# shield_SIM7000E.net
KiCad netlist of a schematic drawn in EAGLE
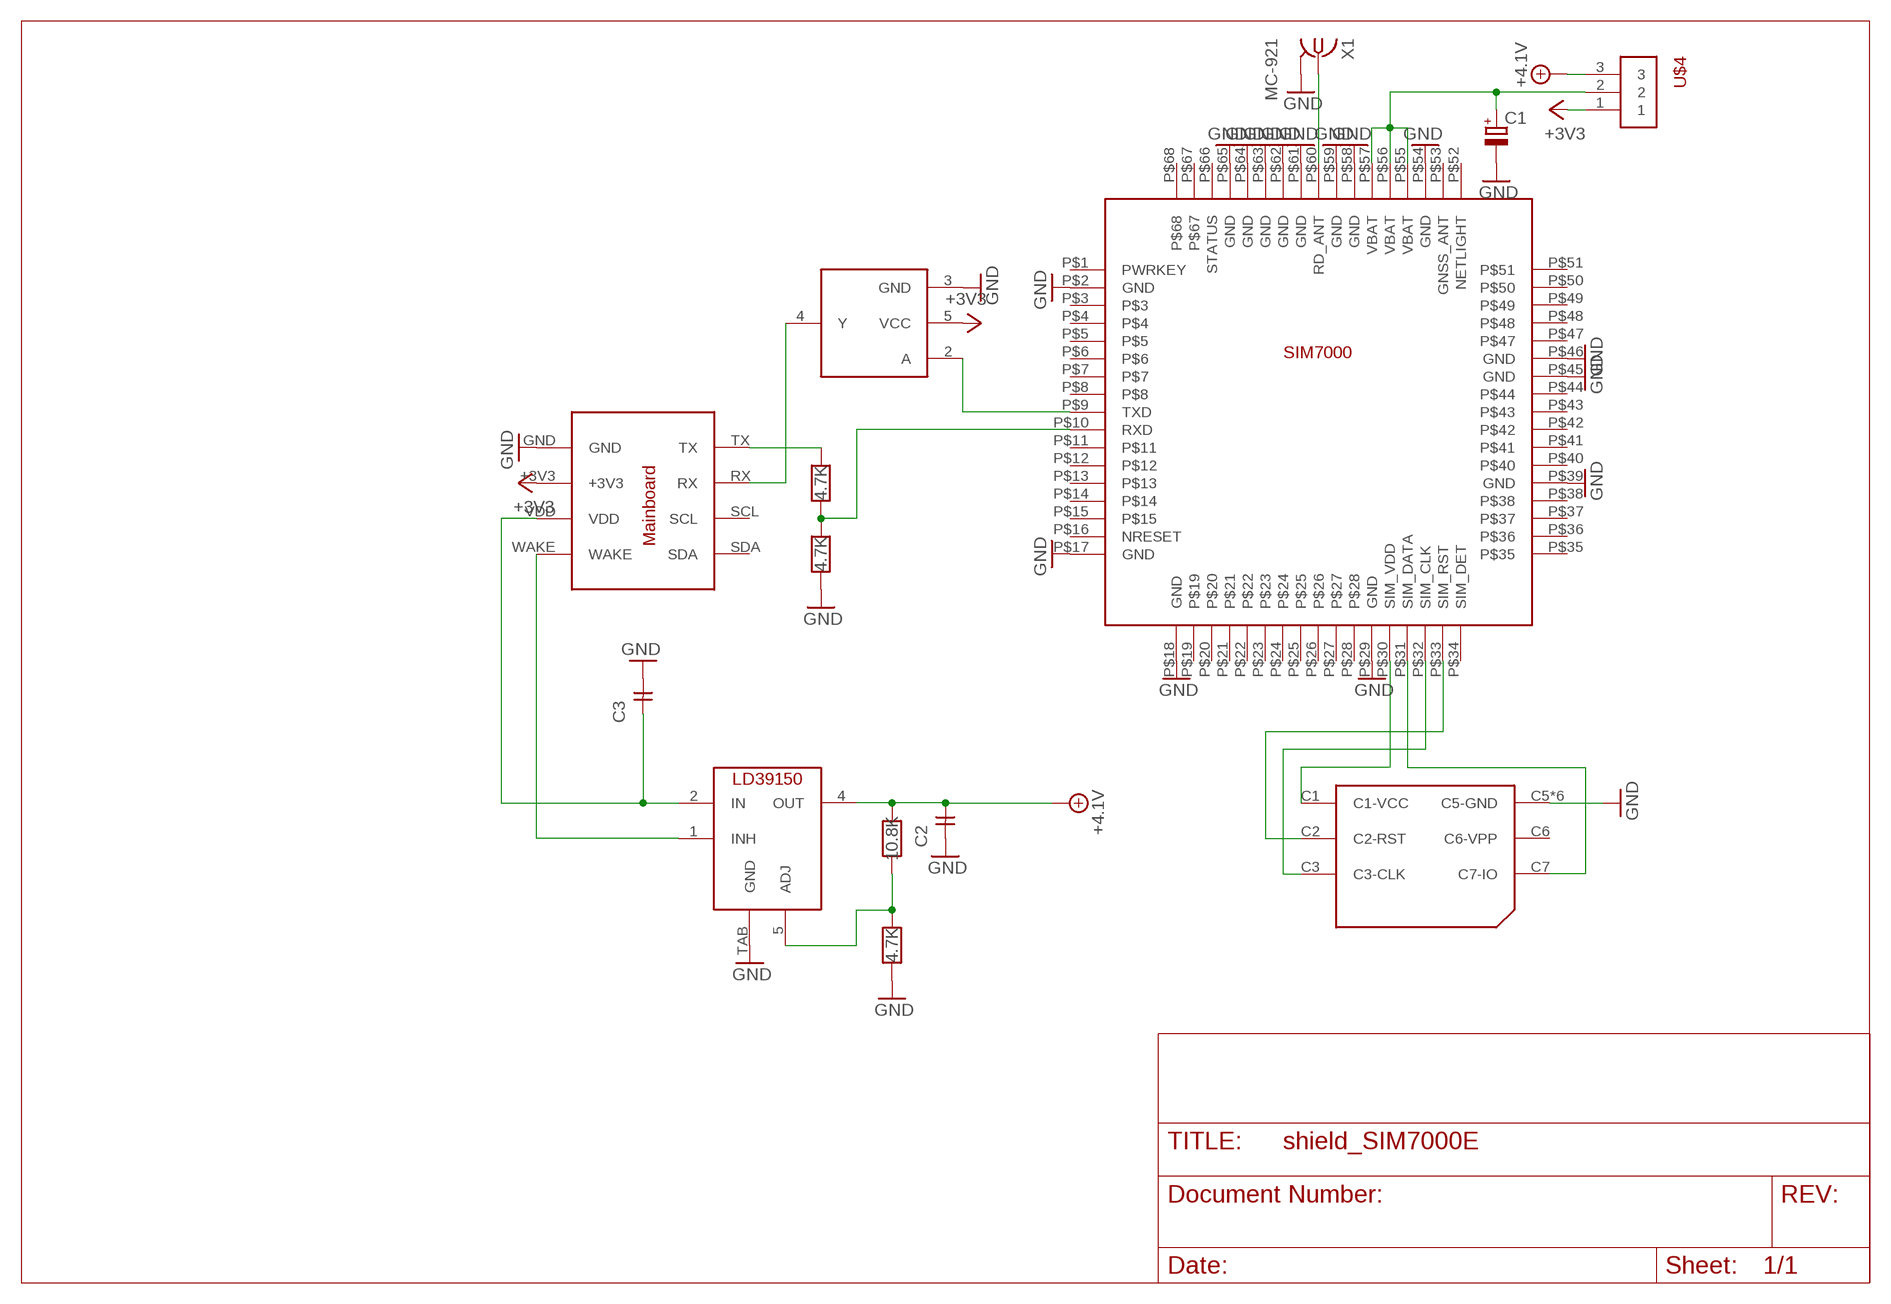
[diagram p0: schematic, sheet 1]

(export (version "E")
  (design (tool "Eeschema 10.0.6"))
  (components
    (comp (ref "C1")
      (value "CPOL-EUE5-13")
      (footprint "eagle-import:E5-13")
      (libsource (lib "eagle-import") (part "CPOL-EUE5-13"))
    )
    (comp (ref "C2")
      (value "CSMD_1206")
      (footprint "eagle-import:SMD_RC_1206")
      (libsource (lib "eagle-import") (part "CSMD_1206"))
    )
    (comp (ref "C3")
      (value "CSMD_1206")
      (footprint "eagle-import:SMD_RC_1206")
      (libsource (lib "eagle-import") (part "CSMD_1206"))
    )
    (comp (ref "R1")
      (value "10.8K")
      (footprint "eagle-import:SMD_RC_1206")
      (libsource (lib "eagle-import") (part "RSMD_1206"))
    )
    (comp (ref "R2")
      (value "4.7K")
      (footprint "eagle-import:SMD_RC_1206")
      (libsource (lib "eagle-import") (part "RSMD_1206"))
    )
    (comp (ref "R3")
      (value "4.7K")
      (footprint "eagle-import:SMD_RC_1206")
      (libsource (lib "eagle-import") (part "RSMD_1206"))
    )
    (comp (ref "R4")
      (value "4.7K")
      (footprint "eagle-import:SMD_RC_1206")
      (libsource (lib "eagle-import") (part "RSMD_1206"))
    )
    (comp (ref "U$1")
      (value "SHIELD")
      (footprint "eagle-import:SHIELD")
      (libsource (lib "eagle-import") (part "SHIELD"))
    )
    (comp (ref "U$2")
      (value "LD39150PT-R")
      (footprint "eagle-import:PPAK")
      (libsource (lib "eagle-import") (part "LD39150PT-R"))
    )
    (comp (ref "U$3")
      (value "SIM7000")
      (footprint "eagle-import:SIM7000")
      (libsource (lib "eagle-import") (part "SIM7000"))
    )
    (comp (ref "U$4")
      (value "HEADER_1X3")
      (footprint "eagle-import:HEADER_1X3")
      (libsource (lib "eagle-import") (part "HEADER_1X3"))
    )
    (comp (ref "U$5")
      (value "SN75LV1T34")
      (footprint "eagle-import:SOT23-5L-SIMPLE")
      (libsource (lib "eagle-import") (part "SN75LV1T34"))
    )
    (comp (ref "U$6")
      (value "SIM_SCYT")
      (footprint "eagle-import:SIM_SCYT")
      (libsource (lib "eagle-import") (part "SIM_SCYT"))
    )
    (comp (ref "X1")
      (value "MC-921")
      (footprint "eagle-import:MC-921")
      (libsource (lib "eagle-import") (part "MC-921"))
    )
  )
  (nets
    (net (code "1") (name "+3V3") (class "Default")
      (node (ref "U$1") (pin "+3V3") (pinfunction "+3V3_+3V3") (pintype "power_in"))
      (node (ref "U$4") (pin "1") (pinfunction "1_1") (pintype "passive"))
      (node (ref "U$5") (pin "5") (pinfunction "VCC_5") (pintype "bidirectional"))
    )
    (net (code "2") (name "+4.1V") (class "Default")
      (node (ref "C2") (pin "P$2") (pinfunction "2_P$2") (pintype "passive"))
      (node (ref "R1") (pin "P$1") (pinfunction "P$1_P$1") (pintype "passive"))
      (node (ref "U$2") (pin "4") (pinfunction "OUT_4") (pintype "power_in"))
      (node (ref "U$4") (pin "3") (pinfunction "3_3") (pintype "passive"))
    )
    (net (code "3") (name "GND") (class "Default")
      (node (ref "C1") (pin "-") (pinfunction "-_-") (pintype "passive"))
      (node (ref "C2") (pin "P$1") (pinfunction "1_P$1") (pintype "passive"))
      (node (ref "C3") (pin "P$2") (pinfunction "2_P$2") (pintype "passive"))
      (node (ref "R2") (pin "P$2") (pinfunction "P$2_P$2") (pintype "passive"))
      (node (ref "R4") (pin "P$1") (pinfunction "P$1_P$1") (pintype "passive"))
      (node (ref "U$1") (pin "GND") (pinfunction "GND_GND") (pintype "power_in"))
      (node (ref "U$2") (pin "TAB") (pinfunction "GND_TAB") (pintype "power_in"))
      (node (ref "U$3") (pin "P$17") (pinfunction "GND_P$17") (pintype "power_in"))
      (node (ref "U$3") (pin "P$18") (pinfunction "GND_P$18") (pintype "bidirectional"))
      (node (ref "U$3") (pin "P$2") (pinfunction "GND_P$2") (pintype "power_in"))
      (node (ref "U$3") (pin "P$29") (pinfunction "GND_P$29") (pintype "bidirectional"))
      (node (ref "U$3") (pin "P$39") (pinfunction "GND_P$39") (pintype "bidirectional"))
      (node (ref "U$3") (pin "P$45") (pinfunction "GND_P$45") (pintype "bidirectional"))
      (node (ref "U$3") (pin "P$46") (pinfunction "GND_P$46") (pintype "bidirectional"))
      (node (ref "U$3") (pin "P$54") (pinfunction "GND_P$54") (pintype "bidirectional"))
      (node (ref "U$3") (pin "P$58") (pinfunction "GND_P$58") (pintype "bidirectional"))
      (node (ref "U$3") (pin "P$59") (pinfunction "GND_P$59") (pintype "bidirectional"))
      (node (ref "U$3") (pin "P$61") (pinfunction "GND_P$61") (pintype "bidirectional"))
      (node (ref "U$3") (pin "P$62") (pinfunction "GND_P$62") (pintype "bidirectional"))
      (node (ref "U$3") (pin "P$63") (pinfunction "GND_P$63") (pintype "bidirectional"))
      (node (ref "U$3") (pin "P$64") (pinfunction "GND_P$64") (pintype "bidirectional"))
      (node (ref "U$3") (pin "P$65") (pinfunction "GND_P$65") (pintype "bidirectional"))
      (node (ref "U$5") (pin "3") (pinfunction "GND_3") (pintype "bidirectional"))
      (node (ref "U$6") (pin "C5") (pinfunction "C5-GND_C5") (pintype "bidirectional"))
      (node (ref "U$6") (pin "GND@1") (pinfunction "C5-GND_GND@1") (pintype "bidirectional"))
      (node (ref "U$6") (pin "GND@2") (pinfunction "C5-GND_GND@2") (pintype "bidirectional"))
      (node (ref "U$6") (pin "GND@3") (pinfunction "C5-GND_GND@3") (pintype "bidirectional"))
      (node (ref "U$6") (pin "GND@4") (pinfunction "C5-GND_GND@4") (pintype "bidirectional"))
      (node (ref "U$6") (pin "GND@5") (pinfunction "C5-GND_GND@5") (pintype "bidirectional"))
      (node (ref "X1") (pin "2@1") (pinfunction "GND_2@1") (pintype "passive"))
      (node (ref "X1") (pin "2@2") (pinfunction "GND_2@2") (pintype "passive"))
    )
    (net (code "4") (name "Net-(C1-Pad+)") (class "Default")
      (node (ref "C1") (pin "+") (pinfunction "+_+") (pintype "passive"))
      (node (ref "U$3") (pin "P$55") (pinfunction "VBAT_P$55") (pintype "bidirectional"))
      (node (ref "U$3") (pin "P$56") (pinfunction "VBAT_P$56") (pintype "bidirectional"))
      (node (ref "U$3") (pin "P$57") (pinfunction "VBAT_P$57") (pintype "bidirectional"))
      (node (ref "U$4") (pin "2") (pinfunction "2_2") (pintype "passive"))
    )
    (net (code "5") (name "Net-(C3-1)") (class "Default")
      (node (ref "C3") (pin "P$1") (pinfunction "1_P$1") (pintype "passive"))
      (node (ref "U$1") (pin "VDD") (pinfunction "VDD_VDD") (pintype "power_in"))
      (node (ref "U$2") (pin "2") (pinfunction "IN_2") (pintype "power_in"))
    )
    (net (code "6") (name "Net-(R3-PadP$2)") (class "Default")
      (node (ref "R3") (pin "P$2") (pinfunction "P$2_P$2") (pintype "passive"))
      (node (ref "U$1") (pin "TX") (pinfunction "TX_TX") (pintype "output"))
    )
    (net (code "7") (name "Net-(U$2-ADJ)") (class "Default")
      (node (ref "R1") (pin "P$2") (pinfunction "P$2_P$2") (pintype "passive"))
      (node (ref "R2") (pin "P$1") (pinfunction "P$1_P$1") (pintype "passive"))
      (node (ref "U$2") (pin "5") (pinfunction "ADJ_5") (pintype "input"))
    )
    (net (code "8") (name "Net-(U$2-INH)") (class "Default")
      (node (ref "U$1") (pin "WAKE") (pinfunction "WAKE_WAKE") (pintype "output"))
      (node (ref "U$2") (pin "1") (pinfunction "INH_1") (pintype "input"))
    )
    (net (code "9") (name "Net-(U$3-RD_ANT)") (class "Default")
      (node (ref "U$3") (pin "P$60") (pinfunction "RD_ANT_P$60") (pintype "bidirectional"))
      (node (ref "X1") (pin "1") (pinfunction "1_1") (pintype "passive"))
    )
    (net (code "10") (name "Net-(U$3-RXD)") (class "Default")
      (node (ref "R3") (pin "P$1") (pinfunction "P$1_P$1") (pintype "passive"))
      (node (ref "R4") (pin "P$2") (pinfunction "P$2_P$2") (pintype "passive"))
      (node (ref "U$3") (pin "P$10") (pinfunction "RXD_P$10") (pintype "bidirectional"))
    )
    (net (code "11") (name "Net-(U$3-SIM_CLK)") (class "Default")
      (node (ref "U$3") (pin "P$32") (pinfunction "SIM_CLK_P$32") (pintype "bidirectional"))
      (node (ref "U$6") (pin "C3") (pinfunction "C3-CLK_C3") (pintype "bidirectional"))
    )
    (net (code "12") (name "Net-(U$3-SIM_DATA)") (class "Default")
      (node (ref "U$3") (pin "P$31") (pinfunction "SIM_DATA_P$31") (pintype "bidirectional"))
      (node (ref "U$6") (pin "C7") (pinfunction "C7-IO_C7") (pintype "bidirectional"))
    )
    (net (code "13") (name "Net-(U$3-SIM_RST)") (class "Default")
      (node (ref "U$3") (pin "P$33") (pinfunction "SIM_RST_P$33") (pintype "bidirectional"))
      (node (ref "U$6") (pin "C2") (pinfunction "C2-RST_C2") (pintype "bidirectional"))
    )
    (net (code "14") (name "Net-(U$3-SIM_VDD)") (class "Default")
      (node (ref "U$3") (pin "P$30") (pinfunction "SIM_VDD_P$30") (pintype "bidirectional"))
      (node (ref "U$6") (pin "C1") (pinfunction "C1-VCC_C1") (pintype "bidirectional"))
    )
    (net (code "15") (name "Net-(U$3-TXD)") (class "Default")
      (node (ref "U$3") (pin "P$9") (pinfunction "TXD_P$9") (pintype "bidirectional"))
      (node (ref "U$5") (pin "2") (pinfunction "A_2") (pintype "bidirectional"))
    )
    (net (code "16") (name "Net-(U$5-Y)") (class "Default")
      (node (ref "U$1") (pin "RX") (pinfunction "RX_RX") (pintype "input"))
      (node (ref "U$5") (pin "4") (pinfunction "Y_4") (pintype "bidirectional"))
    )
    (net (code "17") (name "unconnected-(U$1-PadSCL)") (class "Default")
      (node (ref "U$1") (pin "SCL") (pinfunction "SCL_SCL") (pintype "output"))
    )
    (net (code "18") (name "unconnected-(U$1-PadSDA)") (class "Default")
      (node (ref "U$1") (pin "SDA") (pinfunction "SDA_SDA") (pintype "bidirectional"))
    )
    (net (code "19") (name "unconnected-(U$3-GNSS_ANT-PadP$53)") (class "Default")
      (node (ref "U$3") (pin "P$53") (pinfunction "GNSS_ANT_P$53") (pintype "bidirectional"))
    )
    (net (code "20") (name "unconnected-(U$3-NETLIGHT-PadP$52)") (class "Default")
      (node (ref "U$3") (pin "P$52") (pinfunction "NETLIGHT_P$52") (pintype "bidirectional"))
    )
    (net (code "21") (name "unconnected-(U$3-NRESET-PadP$16)") (class "Default")
      (node (ref "U$3") (pin "P$16") (pinfunction "NRESET_P$16") (pintype "bidirectional"))
    )
    (net (code "22") (name "unconnected-(U$3-PWRKEY-PadP$1)") (class "Default")
      (node (ref "U$3") (pin "P$1") (pinfunction "PWRKEY_P$1") (pintype "bidirectional"))
    )
    (net (code "23") (name "unconnected-(U$3-PadP$3)") (class "Default")
      (node (ref "U$3") (pin "P$3") (pinfunction "P$3_P$3") (pintype "bidirectional"))
    )
    (net (code "24") (name "unconnected-(U$3-PadP$4)") (class "Default")
      (node (ref "U$3") (pin "P$4") (pinfunction "P$4_P$4") (pintype "bidirectional"))
    )
    (net (code "25") (name "unconnected-(U$3-PadP$5)") (class "Default")
      (node (ref "U$3") (pin "P$5") (pinfunction "P$5_P$5") (pintype "bidirectional"))
    )
    (net (code "26") (name "unconnected-(U$3-PadP$6)") (class "Default")
      (node (ref "U$3") (pin "P$6") (pinfunction "P$6_P$6") (pintype "bidirectional"))
    )
    (net (code "27") (name "unconnected-(U$3-PadP$7)") (class "Default")
      (node (ref "U$3") (pin "P$7") (pinfunction "P$7_P$7") (pintype "bidirectional"))
    )
    (net (code "28") (name "unconnected-(U$3-PadP$8)") (class "Default")
      (node (ref "U$3") (pin "P$8") (pinfunction "P$8_P$8") (pintype "bidirectional"))
    )
    (net (code "29") (name "unconnected-(U$3-PadP$11)") (class "Default")
      (node (ref "U$3") (pin "P$11") (pinfunction "P$11_P$11") (pintype "bidirectional"))
    )
    (net (code "30") (name "unconnected-(U$3-PadP$12)") (class "Default")
      (node (ref "U$3") (pin "P$12") (pinfunction "P$12_P$12") (pintype "bidirectional"))
    )
    (net (code "31") (name "unconnected-(U$3-PadP$13)") (class "Default")
      (node (ref "U$3") (pin "P$13") (pinfunction "P$13_P$13") (pintype "bidirectional"))
    )
    (net (code "32") (name "unconnected-(U$3-PadP$14)") (class "Default")
      (node (ref "U$3") (pin "P$14") (pinfunction "P$14_P$14") (pintype "bidirectional"))
    )
    (net (code "33") (name "unconnected-(U$3-PadP$15)") (class "Default")
      (node (ref "U$3") (pin "P$15") (pinfunction "P$15_P$15") (pintype "bidirectional"))
    )
    (net (code "34") (name "unconnected-(U$3-PadP$19)") (class "Default")
      (node (ref "U$3") (pin "P$19") (pinfunction "P$19_P$19") (pintype "bidirectional"))
    )
    (net (code "35") (name "unconnected-(U$3-PadP$20)") (class "Default")
      (node (ref "U$3") (pin "P$20") (pinfunction "P$20_P$20") (pintype "bidirectional"))
    )
    (net (code "36") (name "unconnected-(U$3-PadP$21)") (class "Default")
      (node (ref "U$3") (pin "P$21") (pinfunction "P$21_P$21") (pintype "bidirectional"))
    )
    (net (code "37") (name "unconnected-(U$3-PadP$22)") (class "Default")
      (node (ref "U$3") (pin "P$22") (pinfunction "P$22_P$22") (pintype "bidirectional"))
    )
    (net (code "38") (name "unconnected-(U$3-PadP$23)") (class "Default")
      (node (ref "U$3") (pin "P$23") (pinfunction "P$23_P$23") (pintype "bidirectional"))
    )
    (net (code "39") (name "unconnected-(U$3-PadP$24)") (class "Default")
      (node (ref "U$3") (pin "P$24") (pinfunction "P$24_P$24") (pintype "bidirectional"))
    )
    (net (code "40") (name "unconnected-(U$3-PadP$25)") (class "Default")
      (node (ref "U$3") (pin "P$25") (pinfunction "P$25_P$25") (pintype "bidirectional"))
    )
    (net (code "41") (name "unconnected-(U$3-PadP$26)") (class "Default")
      (node (ref "U$3") (pin "P$26") (pinfunction "P$26_P$26") (pintype "bidirectional"))
    )
    (net (code "42") (name "unconnected-(U$3-PadP$27)") (class "Default")
      (node (ref "U$3") (pin "P$27") (pinfunction "P$27_P$27") (pintype "bidirectional"))
    )
    (net (code "43") (name "unconnected-(U$3-PadP$28)") (class "Default")
      (node (ref "U$3") (pin "P$28") (pinfunction "P$28_P$28") (pintype "bidirectional"))
    )
    (net (code "44") (name "unconnected-(U$3-PadP$35)") (class "Default")
      (node (ref "U$3") (pin "P$35") (pinfunction "P$35_P$35") (pintype "bidirectional"))
    )
    (net (code "45") (name "unconnected-(U$3-PadP$36)") (class "Default")
      (node (ref "U$3") (pin "P$36") (pinfunction "P$36_P$36") (pintype "bidirectional"))
    )
    (net (code "46") (name "unconnected-(U$3-PadP$37)") (class "Default")
      (node (ref "U$3") (pin "P$37") (pinfunction "P$37_P$37") (pintype "bidirectional"))
    )
    (net (code "47") (name "unconnected-(U$3-PadP$38)") (class "Default")
      (node (ref "U$3") (pin "P$38") (pinfunction "P$38_P$38") (pintype "bidirectional"))
    )
    (net (code "48") (name "unconnected-(U$3-PadP$40)") (class "Default")
      (node (ref "U$3") (pin "P$40") (pinfunction "P$40_P$40") (pintype "bidirectional"))
    )
    (net (code "49") (name "unconnected-(U$3-PadP$41)") (class "Default")
      (node (ref "U$3") (pin "P$41") (pinfunction "P$41_P$41") (pintype "bidirectional"))
    )
    (net (code "50") (name "unconnected-(U$3-PadP$42)") (class "Default")
      (node (ref "U$3") (pin "P$42") (pinfunction "P$42_P$42") (pintype "bidirectional"))
    )
    (net (code "51") (name "unconnected-(U$3-PadP$43)") (class "Default")
      (node (ref "U$3") (pin "P$43") (pinfunction "P$43_P$43") (pintype "bidirectional"))
    )
    (net (code "52") (name "unconnected-(U$3-PadP$44)") (class "Default")
      (node (ref "U$3") (pin "P$44") (pinfunction "P$44_P$44") (pintype "bidirectional"))
    )
    (net (code "53") (name "unconnected-(U$3-PadP$47)") (class "Default")
      (node (ref "U$3") (pin "P$47") (pinfunction "P$47_P$47") (pintype "bidirectional"))
    )
    (net (code "54") (name "unconnected-(U$3-PadP$48)") (class "Default")
      (node (ref "U$3") (pin "P$48") (pinfunction "P$48_P$48") (pintype "bidirectional"))
    )
    (net (code "55") (name "unconnected-(U$3-PadP$49)") (class "Default")
      (node (ref "U$3") (pin "P$49") (pinfunction "P$49_P$49") (pintype "bidirectional"))
    )
    (net (code "56") (name "unconnected-(U$3-PadP$50)") (class "Default")
      (node (ref "U$3") (pin "P$50") (pinfunction "P$50_P$50") (pintype "bidirectional"))
    )
    (net (code "57") (name "unconnected-(U$3-PadP$51)") (class "Default")
      (node (ref "U$3") (pin "P$51") (pinfunction "P$51_P$51") (pintype "bidirectional"))
    )
    (net (code "58") (name "unconnected-(U$3-PadP$67)") (class "Default")
      (node (ref "U$3") (pin "P$67") (pinfunction "P$67_P$67") (pintype "bidirectional"))
    )
    (net (code "59") (name "unconnected-(U$3-PadP$68)") (class "Default")
      (node (ref "U$3") (pin "P$68") (pinfunction "P$68_P$68") (pintype "bidirectional"))
    )
    (net (code "60") (name "unconnected-(U$3-SIM_DET-PadP$34)") (class "Default")
      (node (ref "U$3") (pin "P$34") (pinfunction "SIM_DET_P$34") (pintype "bidirectional"))
    )
    (net (code "61") (name "unconnected-(U$3-STATUS-PadP$66)") (class "Default")
      (node (ref "U$3") (pin "P$66") (pinfunction "STATUS_P$66") (pintype "bidirectional"))
    )
    (net (code "62") (name "unconnected-(U$6-C6-VPP-PadC6)") (class "Default")
      (node (ref "U$6") (pin "C6") (pinfunction "C6-VPP_C6") (pintype "bidirectional"))
    )
  )
)
